# as14120_x31_usb.net
KiCad netlist of a schematic drawn in Altium Designer
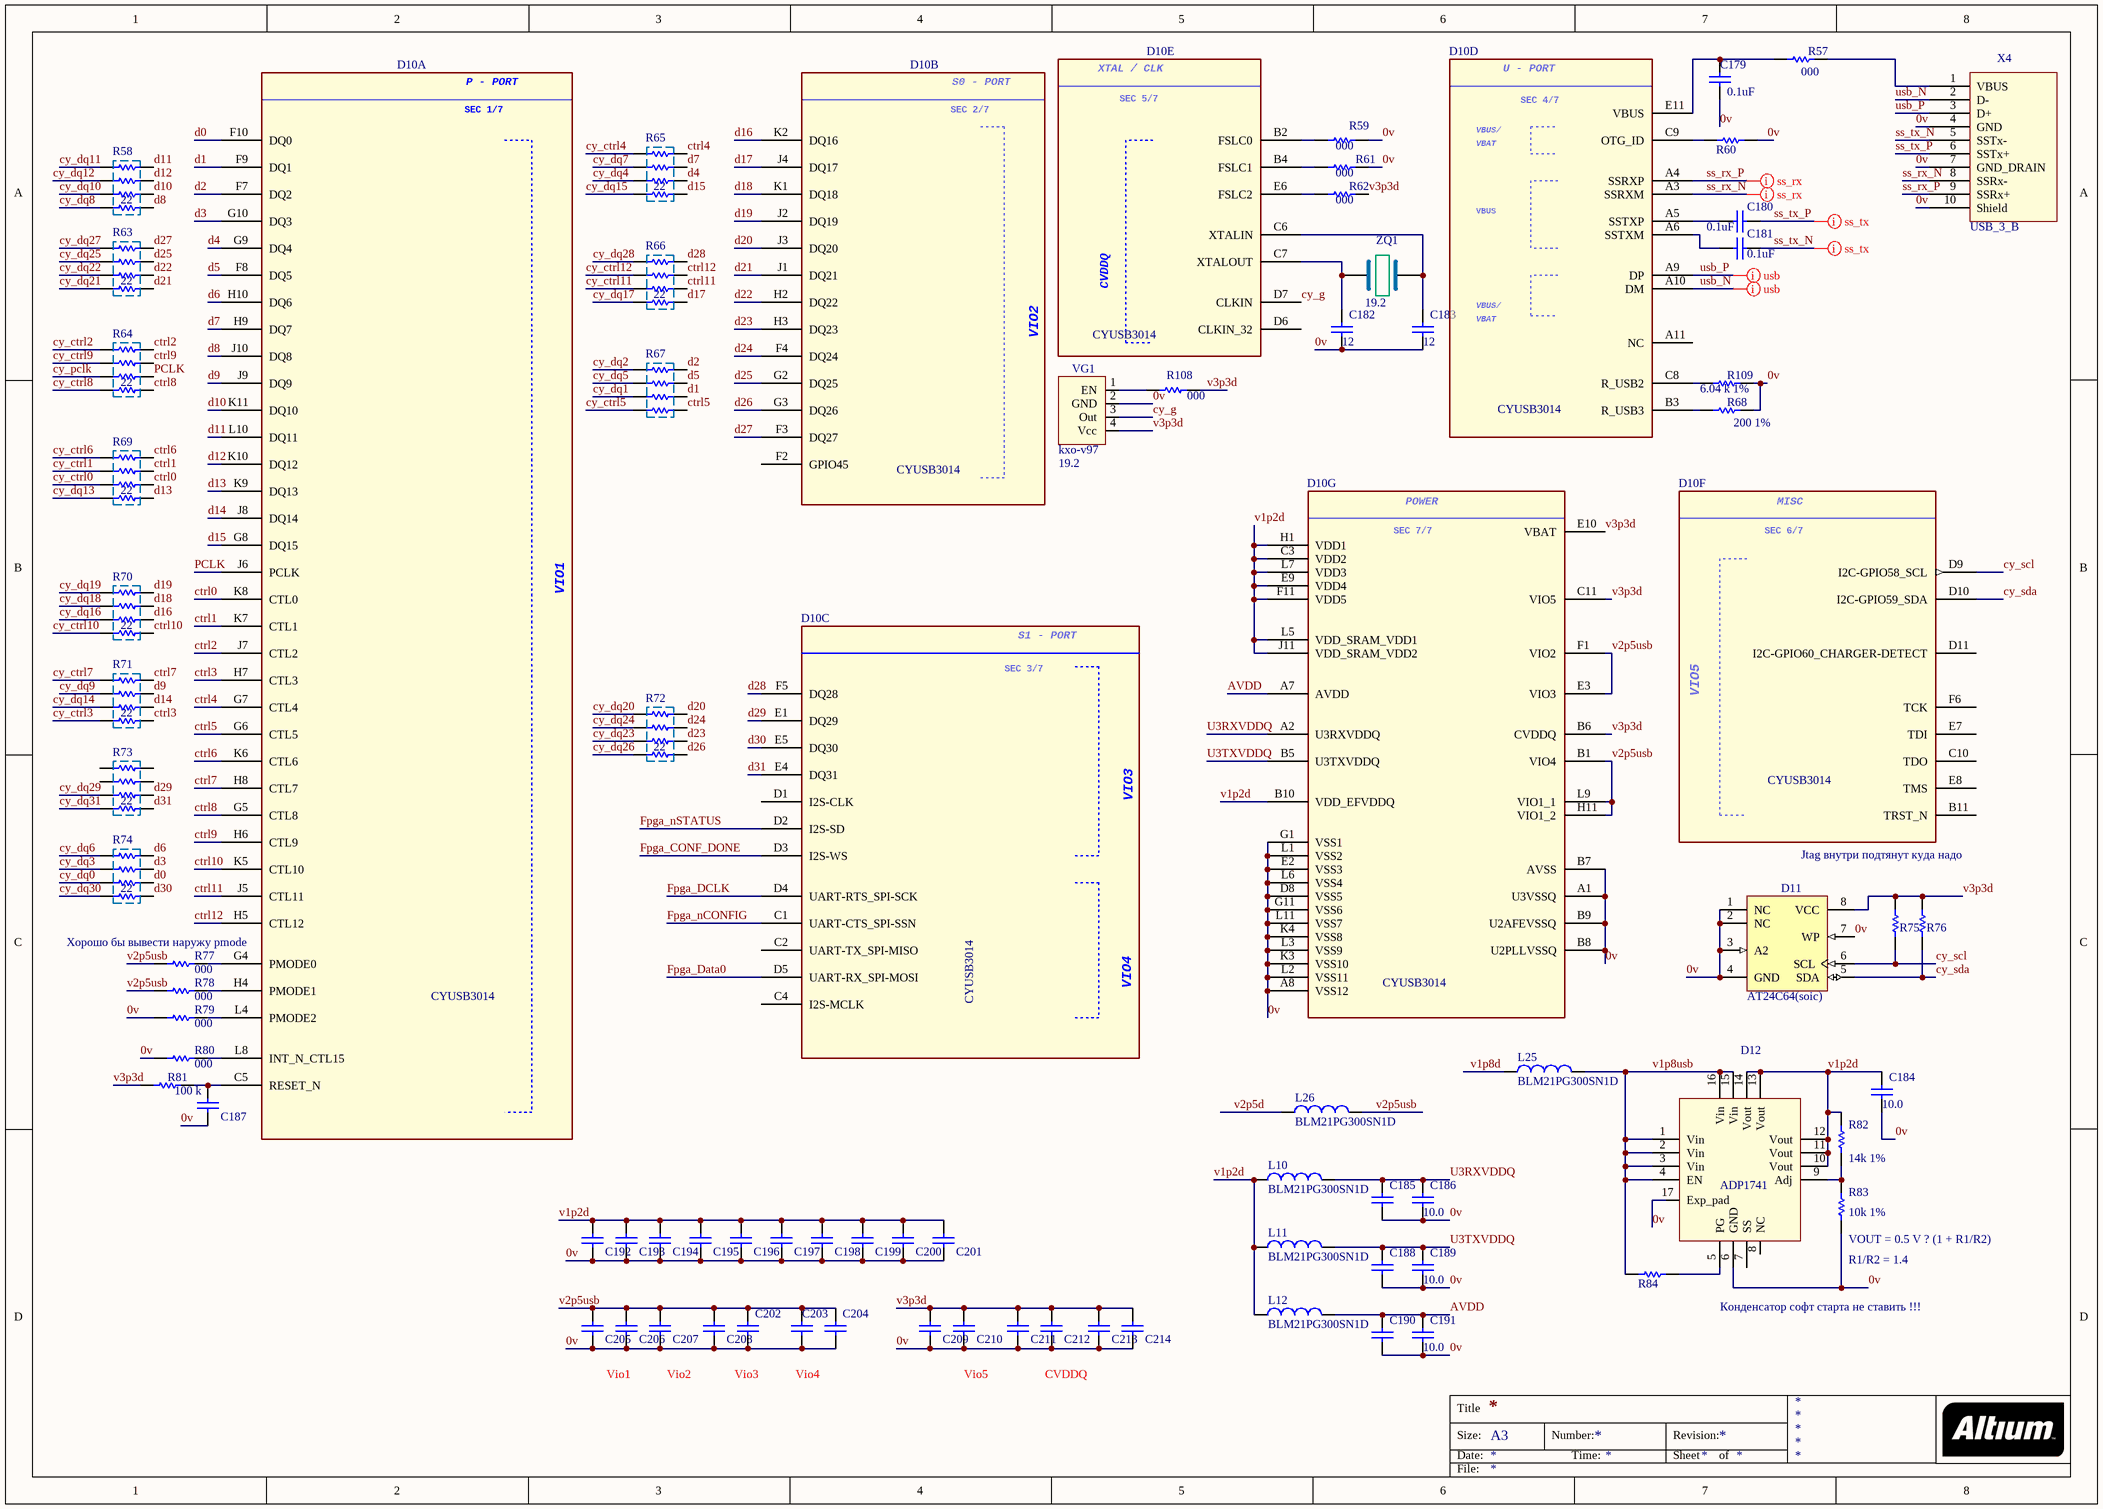
[diagram p0: as14120_x31_usb.SchDoc]

(export (version "E")
  (design (tool "Eeschema 10.0.6"))
  (components
    (comp (ref "C179")
      (value "0.1uF")
      (footprint "CAPC0402(1005)60_M")
      (description "CAP 1uF 10V ±20% 0402 (1005 Metric) Thickness 0.6mm SMD")
      (fields (field (name "TOLERANCE") "±20%") (field (name "Comment") "CAP 1uF 10V 0402(1005)"))
      (libsource (lib "as14120") (part "CAP_0402"))
    )
    (comp (ref "C180")
      (value "0.1uF")
      (footprint "CAPC0402(1005)60_M")
      (description "CAP 1uF 10V ±20% 0402 (1005 Metric) Thickness 0.6mm SMD")
      (fields (field (name "TOLERANCE") "±20%") (field (name "Comment") "CAP 1uF 10V 0402(1005)"))
      (libsource (lib "as14120") (part "CAP_0402"))
    )
    (comp (ref "C181")
      (value "0.1uF")
      (footprint "CAPC0402(1005)60_M")
      (description "CAP 1uF 10V ±20% 0402 (1005 Metric) Thickness 0.6mm SMD")
      (fields (field (name "TOLERANCE") "±20%") (field (name "Comment") "CAP 1uF 10V 0402(1005)"))
      (libsource (lib "as14120") (part "CAP_0402"))
    )
    (comp (ref "C182")
      (value "12")
      (footprint "CAPC0805(2012)100_N")
      (fields (field (name "Comment") "CAP_0805"))
      (libsource (lib "as14120") (part "CAP_0805"))
    )
    (comp (ref "C183")
      (value "12")
      (footprint "CAPC0805(2012)100_N")
      (fields (field (name "Comment") "CAP_0805"))
      (libsource (lib "as14120") (part "CAP_0805"))
    )
    (comp (ref "C184")
      (value "10.0")
      (footprint "CAPC0805(2012)100_N")
      (fields (field (name "Comment") "CAP_0805"))
      (libsource (lib "as14120") (part "CAP_0805"))
    )
    (comp (ref "C185")
      (value "CAP 1uF 10V 0402(1005)")
      (footprint "CAPC0402(1005)60_M")
      (description "CAP 1uF 10V ±20% 0402 (1005 Metric) Thickness 0.6mm SMD")
      (fields (field (name "TOLERANCE") "±20%"))
      (libsource (lib "as14120") (part "CAP_0402"))
    )
    (comp (ref "C186")
      (value "10.0")
      (footprint "CAPC0805(2012)100_N")
      (fields (field (name "Comment") "CAP_0805"))
      (libsource (lib "as14120") (part "CAP_0805"))
    )
    (comp (ref "C187")
      (value "CAP 1uF 10V 0402(1005)")
      (footprint "CAPC0402(1005)60_M")
      (description "CAP 1uF 10V ±20% 0402 (1005 Metric) Thickness 0.6mm SMD")
      (fields (field (name "TOLERANCE") "±20%"))
      (libsource (lib "as14120") (part "CAP_0402"))
    )
    (comp (ref "C188")
      (value "CAP 1uF 10V 0402(1005)")
      (footprint "CAPC0402(1005)60_M")
      (description "CAP 1uF 10V ±20% 0402 (1005 Metric) Thickness 0.6mm SMD")
      (fields (field (name "TOLERANCE") "±20%"))
      (libsource (lib "as14120") (part "CAP_0402"))
    )
    (comp (ref "C189")
      (value "10.0")
      (footprint "CAPC0805(2012)100_N")
      (fields (field (name "Comment") "CAP_0805"))
      (libsource (lib "as14120") (part "CAP_0805"))
    )
    (comp (ref "C190")
      (value "CAP 1uF 10V 0402(1005)")
      (footprint "CAPC0402(1005)60_M")
      (description "CAP 1uF 10V ±20% 0402 (1005 Metric) Thickness 0.6mm SMD")
      (fields (field (name "TOLERANCE") "±20%"))
      (libsource (lib "as14120") (part "CAP_0402"))
    )
    (comp (ref "C191")
      (value "10.0")
      (footprint "CAPC0805(2012)100_N")
      (fields (field (name "Comment") "CAP_0805"))
      (libsource (lib "as14120") (part "CAP_0805"))
    )
    (comp (ref "C192")
      (value "CAP 1uF 10V 0402(1005)")
      (footprint "CAPC0402(1005)60_M")
      (description "CAP 1uF 10V ±20% 0402 (1005 Metric) Thickness 0.6mm SMD")
      (fields (field (name "TOLERANCE") "±20%"))
      (libsource (lib "as14120") (part "CAP_0402"))
    )
    (comp (ref "C193")
      (value "CAP 1uF 10V 0402(1005)")
      (footprint "CAPC0402(1005)60_M")
      (description "CAP 1uF 10V ±20% 0402 (1005 Metric) Thickness 0.6mm SMD")
      (fields (field (name "TOLERANCE") "±20%"))
      (libsource (lib "as14120") (part "CAP_0402"))
    )
    (comp (ref "C194")
      (value "CAP 1uF 10V 0402(1005)")
      (footprint "CAPC0402(1005)60_M")
      (description "CAP 1uF 10V ±20% 0402 (1005 Metric) Thickness 0.6mm SMD")
      (fields (field (name "TOLERANCE") "±20%"))
      (libsource (lib "as14120") (part "CAP_0402"))
    )
    (comp (ref "C195")
      (value "CAP 1uF 10V 0402(1005)")
      (footprint "CAPC0402(1005)60_M")
      (description "CAP 1uF 10V ±20% 0402 (1005 Metric) Thickness 0.6mm SMD")
      (fields (field (name "TOLERANCE") "±20%"))
      (libsource (lib "as14120") (part "CAP_0402"))
    )
    (comp (ref "C196")
      (value "CAP 1uF 10V 0402(1005)")
      (footprint "CAPC0402(1005)60_M")
      (description "CAP 1uF 10V ±20% 0402 (1005 Metric) Thickness 0.6mm SMD")
      (fields (field (name "TOLERANCE") "±20%"))
      (libsource (lib "as14120") (part "CAP_0402"))
    )
    (comp (ref "C197")
      (value "CAP 1uF 10V 0402(1005)")
      (footprint "CAPC0402(1005)60_M")
      (description "CAP 1uF 10V ±20% 0402 (1005 Metric) Thickness 0.6mm SMD")
      (fields (field (name "TOLERANCE") "±20%"))
      (libsource (lib "as14120") (part "CAP_0402"))
    )
    (comp (ref "C198")
      (value "CAP 1uF 10V 0402(1005)")
      (footprint "CAPC0402(1005)60_M")
      (description "CAP 1uF 10V ±20% 0402 (1005 Metric) Thickness 0.6mm SMD")
      (fields (field (name "TOLERANCE") "±20%"))
      (libsource (lib "as14120") (part "CAP_0402"))
    )
    (comp (ref "C199")
      (value "CAP 1uF 10V 0402(1005)")
      (footprint "CAPC0402(1005)60_M")
      (description "CAP 1uF 10V ±20% 0402 (1005 Metric) Thickness 0.6mm SMD")
      (fields (field (name "TOLERANCE") "±20%"))
      (libsource (lib "as14120") (part "CAP_0402"))
    )
    (comp (ref "C200")
      (value "CAP 1uF 10V 0402(1005)")
      (footprint "CAPC0402(1005)60_M")
      (description "CAP 1uF 10V ±20% 0402 (1005 Metric) Thickness 0.6mm SMD")
      (fields (field (name "TOLERANCE") "±20%"))
      (libsource (lib "as14120") (part "CAP_0402"))
    )
    (comp (ref "C201")
      (value "CAP 1uF 10V 0402(1005)")
      (footprint "CAPC0402(1005)60_M")
      (description "CAP 1uF 10V ±20% 0402 (1005 Metric) Thickness 0.6mm SMD")
      (fields (field (name "TOLERANCE") "±20%"))
      (libsource (lib "as14120") (part "CAP_0402"))
    )
    (comp (ref "C202")
      (value "CAP 1uF 10V 0402(1005)")
      (footprint "CAPC0402(1005)60_M")
      (description "CAP 1uF 10V ±20% 0402 (1005 Metric) Thickness 0.6mm SMD")
      (fields (field (name "TOLERANCE") "±20%"))
      (libsource (lib "as14120") (part "CAP_0402"))
    )
    (comp (ref "C203")
      (value "CAP 1uF 10V 0402(1005)")
      (footprint "CAPC0402(1005)60_M")
      (description "CAP 1uF 10V ±20% 0402 (1005 Metric) Thickness 0.6mm SMD")
      (fields (field (name "TOLERANCE") "±20%"))
      (libsource (lib "as14120") (part "CAP_0402"))
    )
    (comp (ref "C204")
      (value "CAP 1uF 10V 0402(1005)")
      (footprint "CAPC0402(1005)60_M")
      (description "CAP 1uF 10V ±20% 0402 (1005 Metric) Thickness 0.6mm SMD")
      (fields (field (name "TOLERANCE") "±20%"))
      (libsource (lib "as14120") (part "CAP_0402"))
    )
    (comp (ref "C205")
      (value "CAP 1uF 10V 0402(1005)")
      (footprint "CAPC0402(1005)60_M")
      (description "CAP 1uF 10V ±20% 0402 (1005 Metric) Thickness 0.6mm SMD")
      (fields (field (name "TOLERANCE") "±20%"))
      (libsource (lib "as14120") (part "CAP_0402"))
    )
    (comp (ref "C206")
      (value "CAP 1uF 10V 0402(1005)")
      (footprint "CAPC0402(1005)60_M")
      (description "CAP 1uF 10V ±20% 0402 (1005 Metric) Thickness 0.6mm SMD")
      (fields (field (name "TOLERANCE") "±20%"))
      (libsource (lib "as14120") (part "CAP_0402"))
    )
    (comp (ref "C207")
      (value "CAP 1uF 10V 0402(1005)")
      (footprint "CAPC0402(1005)60_M")
      (description "CAP 1uF 10V ±20% 0402 (1005 Metric) Thickness 0.6mm SMD")
      (fields (field (name "TOLERANCE") "±20%"))
      (libsource (lib "as14120") (part "CAP_0402"))
    )
    (comp (ref "C208")
      (value "CAP 1uF 10V 0402(1005)")
      (footprint "CAPC0402(1005)60_M")
      (description "CAP 1uF 10V ±20% 0402 (1005 Metric) Thickness 0.6mm SMD")
      (fields (field (name "TOLERANCE") "±20%"))
      (libsource (lib "as14120") (part "CAP_0402"))
    )
    (comp (ref "C209")
      (value "CAP 1uF 10V 0402(1005)")
      (footprint "CAPC0402(1005)60_M")
      (description "CAP 1uF 10V ±20% 0402 (1005 Metric) Thickness 0.6mm SMD")
      (fields (field (name "TOLERANCE") "±20%"))
      (libsource (lib "as14120") (part "CAP_0402"))
    )
    (comp (ref "C210")
      (value "CAP 1uF 10V 0402(1005)")
      (footprint "CAPC0402(1005)60_M")
      (description "CAP 1uF 10V ±20% 0402 (1005 Metric) Thickness 0.6mm SMD")
      (fields (field (name "TOLERANCE") "±20%"))
      (libsource (lib "as14120") (part "CAP_0402"))
    )
    (comp (ref "C211")
      (value "CAP 1uF 10V 0402(1005)")
      (footprint "CAPC0402(1005)60_M")
      (description "CAP 1uF 10V ±20% 0402 (1005 Metric) Thickness 0.6mm SMD")
      (fields (field (name "TOLERANCE") "±20%"))
      (libsource (lib "as14120") (part "CAP_0402"))
    )
    (comp (ref "C212")
      (value "CAP 1uF 10V 0402(1005)")
      (footprint "CAPC0402(1005)60_M")
      (description "CAP 1uF 10V ±20% 0402 (1005 Metric) Thickness 0.6mm SMD")
      (fields (field (name "TOLERANCE") "±20%"))
      (libsource (lib "as14120") (part "CAP_0402"))
    )
    (comp (ref "C213")
      (value "CAP 1uF 10V 0402(1005)")
      (footprint "CAPC0402(1005)60_M")
      (description "CAP 1uF 10V ±20% 0402 (1005 Metric) Thickness 0.6mm SMD")
      (fields (field (name "TOLERANCE") "±20%"))
      (libsource (lib "as14120") (part "CAP_0402"))
    )
    (comp (ref "C214")
      (value "CAP 1uF 10V 0402(1005)")
      (footprint "CAPC0402(1005)60_M")
      (description "CAP 1uF 10V ±20% 0402 (1005 Metric) Thickness 0.6mm SMD")
      (fields (field (name "TOLERANCE") "±20%"))
      (libsource (lib "as14120") (part "CAP_0402"))
    )
    (comp (ref "D10")
      (value "CYUSB3014")
      (footprint "BGA121C80P11X11")
      (libsource (lib "as14120") (part "CYUSB3014-BZXC"))
    )
    (comp (ref "D11")
      (value "AT24C64(soic)")
      (footprint "8S1_N")
      (libsource (lib "Atmel Serial EEPROM") (part "AT24C08BN-SP25-T"))
    )
    (comp (ref "D12") (value "ADP1741") (footprint "CP-16-4_N") (libsource (lib "as14120") (part "ADP1741")))
    (comp (ref "L10")
      (value "BLM21PG300SN1D")
      (footprint "CAPC0805(2012)100_N")
      (libsource (lib "as14120") (part "Ferrite_beat"))
    )
    (comp (ref "L11")
      (value "BLM21PG300SN1D")
      (footprint "CAPC0805(2012)100_N")
      (libsource (lib "as14120") (part "Ferrite_beat"))
    )
    (comp (ref "L12")
      (value "BLM21PG300SN1D")
      (footprint "CAPC0805(2012)100_N")
      (libsource (lib "as14120") (part "Ferrite_beat"))
    )
    (comp (ref "L25")
      (value "BLM21PG300SN1D")
      (footprint "CAPC0805(2012)100_N")
      (libsource (lib "as14120") (part "Ferrite_beat"))
    )
    (comp (ref "L26")
      (value "BLM21PG300SN1D")
      (footprint "CAPC0805(2012)100_N")
      (libsource (lib "as14120") (part "Ferrite_beat"))
    )
    (comp (ref "R57")
      (value "000")
      (footprint "RESC0805(2012)_L")
      (description "1K 0.125W 1% 0805 (2012 Metric)  SMD")
      (fields (field (name "TOLERANCE") "1 %") (field (name "POWER") "0.125 W"))
      (libsource (lib "as14120") (part "RES_0805"))
    )
    (comp (ref "R58") (value "22") (footprint "CAY16") (libsource (lib "as14120") (part "cay16-J4")))
    (comp (ref "R59")
      (value "000")
      (footprint "RESC0603(1608)_L")
      (description "1K 0.1W 5% 0603 (1608 Metric)  SMD")
      (fields (field (name "TOLERANCE") "5 %") (field (name "POWER") "0.1 W"))
      (libsource (lib "as14120") (part "RES_0603"))
    )
    (comp (ref "R60")
      (value "???")
      (footprint "RESC0603(1608)_L")
      (description "1K 0.1W 5% 0603 (1608 Metric)  SMD")
      (fields (field (name "TOLERANCE") "5 %") (field (name "POWER") "0.1 W"))
      (libsource (lib "as14120") (part "RES_0603"))
    )
    (comp (ref "R61")
      (value "000")
      (footprint "RESC0603(1608)_L")
      (description "1K 0.1W 5% 0603 (1608 Metric)  SMD")
      (fields (field (name "TOLERANCE") "5 %") (field (name "POWER") "0.1 W"))
      (libsource (lib "as14120") (part "RES_0603"))
    )
    (comp (ref "R62")
      (value "000")
      (footprint "RESC0603(1608)_L")
      (description "1K 0.1W 5% 0603 (1608 Metric)  SMD")
      (fields (field (name "TOLERANCE") "5 %") (field (name "POWER") "0.1 W"))
      (libsource (lib "as14120") (part "RES_0603"))
    )
    (comp (ref "R63") (value "22") (footprint "CAY16") (libsource (lib "as14120") (part "cay16-J4")))
    (comp (ref "R64") (value "22") (footprint "CAY16") (libsource (lib "as14120") (part "cay16-J4")))
    (comp (ref "R65") (value "22") (footprint "CAY16") (libsource (lib "as14120") (part "cay16-J4")))
    (comp (ref "R66") (value "22") (footprint "CAY16") (libsource (lib "as14120") (part "cay16-J4")))
    (comp (ref "R67") (value "~") (footprint "CAY16") (libsource (lib "as14120") (part "cay16-J4")))
    (comp (ref "R68")
      (value "200 1%")
      (footprint "RESC0805(2012)_L")
      (description "1K 0.125W 1% 0805 (2012 Metric)  SMD")
      (fields (field (name "TOLERANCE") "1 %") (field (name "POWER") "0.125 W"))
      (libsource (lib "as14120") (part "RES_0805"))
    )
    (comp (ref "R69") (value "22") (footprint "CAY16") (libsource (lib "as14120") (part "cay16-J4")))
    (comp (ref "R70") (value "22") (footprint "CAY16") (libsource (lib "as14120") (part "cay16-J4")))
    (comp (ref "R71") (value "22") (footprint "CAY16") (libsource (lib "as14120") (part "cay16-J4")))
    (comp (ref "R72") (value "22") (footprint "CAY16") (libsource (lib "as14120") (part "cay16-J4")))
    (comp (ref "R73") (value "22") (footprint "CAY16") (libsource (lib "as14120") (part "cay16-J4")))
    (comp (ref "R74") (value "22") (footprint "CAY16") (libsource (lib "as14120") (part "cay16-J4")))
    (comp (ref "R75")
      (value "1K 5% 0603(1608)")
      (footprint "RESC0603(1608)_L")
      (description "1K 0.1W 5% 0603 (1608 Metric)  SMD")
      (fields (field (name "TOLERANCE") "5 %") (field (name "POWER") "0.1 W"))
      (libsource (lib "as14120") (part "RES_0603"))
    )
    (comp (ref "R76")
      (value "1K 5% 0603(1608)")
      (footprint "RESC0603(1608)_L")
      (description "1K 0.1W 5% 0603 (1608 Metric)  SMD")
      (fields (field (name "TOLERANCE") "5 %") (field (name "POWER") "0.1 W"))
      (libsource (lib "as14120") (part "RES_0603"))
    )
    (comp (ref "R77")
      (value "000")
      (footprint "RESC0603(1608)_L")
      (description "1K 0.1W 5% 0603 (1608 Metric)  SMD")
      (fields (field (name "TOLERANCE") "5 %") (field (name "POWER") "0.1 W"))
      (libsource (lib "as14120") (part "RES_0603"))
    )
    (comp (ref "R78")
      (value "000")
      (footprint "RESC0603(1608)_L")
      (description "1K 0.1W 5% 0603 (1608 Metric)  SMD")
      (fields (field (name "TOLERANCE") "5 %") (field (name "POWER") "0.1 W"))
      (libsource (lib "as14120") (part "RES_0603"))
    )
    (comp (ref "R79")
      (value "000")
      (footprint "RESC0603(1608)_L")
      (description "1K 0.1W 5% 0603 (1608 Metric)  SMD")
      (fields (field (name "TOLERANCE") "5 %") (field (name "POWER") "0.1 W"))
      (libsource (lib "as14120") (part "RES_0603"))
    )
    (comp (ref "R80")
      (value "000")
      (footprint "RESC0603(1608)_L")
      (description "1K 0.1W 5% 0603 (1608 Metric)  SMD")
      (fields (field (name "TOLERANCE") "5 %") (field (name "POWER") "0.1 W"))
      (libsource (lib "as14120") (part "RES_0603"))
    )
    (comp (ref "R81")
      (value "100 k")
      (footprint "RESC0603(1608)_L")
      (description "1K 0.1W 5% 0603 (1608 Metric)  SMD")
      (fields (field (name "TOLERANCE") "5 %") (field (name "POWER") "0.1 W"))
      (libsource (lib "as14120") (part "RES_0603"))
    )
    (comp (ref "R82")
      (value "14k 1%")
      (footprint "RESC0805(2012)_L")
      (description "1K 0.125W 1% 0805 (2012 Metric)  SMD")
      (fields (field (name "TOLERANCE") "1 %") (field (name "POWER") "0.125 W"))
      (libsource (lib "as14120") (part "RES_0805"))
    )
    (comp (ref "R83")
      (value "10k 1%")
      (footprint "RESC0805(2012)_L")
      (description "1K 0.125W 1% 0805 (2012 Metric)  SMD")
      (fields (field (name "TOLERANCE") "1 %") (field (name "POWER") "0.125 W"))
      (libsource (lib "as14120") (part "RES_0805"))
    )
    (comp (ref "R84")
      (value "1K 5% 0603(1608)")
      (footprint "RESC0603(1608)_L")
      (description "1K 0.1W 5% 0603 (1608 Metric)  SMD")
      (fields (field (name "TOLERANCE") "5 %") (field (name "POWER") "0.1 W"))
      (libsource (lib "as14120") (part "RES_0603"))
    )
    (comp (ref "R108")
      (value "000")
      (footprint "RESC0603(1608)_L")
      (description "1K 0.1W 5% 0603 (1608 Metric)  SMD")
      (fields (field (name "TOLERANCE") "5 %") (field (name "POWER") "0.1 W"))
      (libsource (lib "as14120") (part "RES_0603"))
    )
    (comp (ref "R109")
      (value "6.04 k 1%")
      (footprint "RESC0805(2012)_L")
      (description "1K 0.125W 1% 0805 (2012 Metric)  SMD")
      (fields (field (name "TOLERANCE") "1 %") (field (name "POWER") "0.125 W"))
      (libsource (lib "as14120") (part "RES_0805"))
    )
    (comp (ref "VG1")
      (value "kxo-v97")
      (footprint "kxo-v97")
      (fields (field (name "ALTIUM_VALUE") "19.2"))
      (libsource (lib "as14120") (part "kxo-v97"))
    )
    (comp (ref "X4") (value "USB_3_B") (footprint "USB3_B") (libsource (lib "as14120") (part "USB_3_B")))
    (comp (ref "ZQ1")
      (value "19.2")
      (footprint "BCY-W2/E4.7")
      (fields (field (name "Comment") "Resonator"))
      (libsource (lib "as14120") (part "Resonator"))
    )
  )
  (nets
    (net (code "1") (name "/0v") (class "Default")
      (node (ref "C179") (pin "2") (pinfunction "2_2") (pintype "passive"))
      (node (ref "C182") (pin "1") (pinfunction "1_1") (pintype "passive"))
      (node (ref "C183") (pin "1") (pinfunction "1_1") (pintype "passive"))
      (node (ref "C184") (pin "1") (pinfunction "1_1") (pintype "passive"))
      (node (ref "C185") (pin "1") (pinfunction "1_1") (pintype "passive"))
      (node (ref "C186") (pin "1") (pinfunction "1_1") (pintype "passive"))
      (node (ref "C187") (pin "1") (pinfunction "1_1") (pintype "passive"))
      (node (ref "C188") (pin "1") (pinfunction "1_1") (pintype "passive"))
      (node (ref "C189") (pin "1") (pinfunction "1_1") (pintype "passive"))
      (node (ref "C190") (pin "1") (pinfunction "1_1") (pintype "passive"))
      (node (ref "C191") (pin "1") (pinfunction "1_1") (pintype "passive"))
      (node (ref "C192") (pin "1") (pinfunction "1_1") (pintype "passive"))
      (node (ref "C193") (pin "1") (pinfunction "1_1") (pintype "passive"))
      (node (ref "C194") (pin "1") (pinfunction "1_1") (pintype "passive"))
      (node (ref "C195") (pin "1") (pinfunction "1_1") (pintype "passive"))
      (node (ref "C196") (pin "1") (pinfunction "1_1") (pintype "passive"))
      (node (ref "C197") (pin "1") (pinfunction "1_1") (pintype "passive"))
      (node (ref "C198") (pin "1") (pinfunction "1_1") (pintype "passive"))
      (node (ref "C199") (pin "1") (pinfunction "1_1") (pintype "passive"))
      (node (ref "C200") (pin "1") (pinfunction "1_1") (pintype "passive"))
      (node (ref "C201") (pin "1") (pinfunction "1_1") (pintype "passive"))
      (node (ref "C202") (pin "1") (pinfunction "1_1") (pintype "passive"))
      (node (ref "C203") (pin "1") (pinfunction "1_1") (pintype "passive"))
      (node (ref "C204") (pin "1") (pinfunction "1_1") (pintype "passive"))
      (node (ref "C205") (pin "1") (pinfunction "1_1") (pintype "passive"))
      (node (ref "C206") (pin "1") (pinfunction "1_1") (pintype "passive"))
      (node (ref "C207") (pin "1") (pinfunction "1_1") (pintype "passive"))
      (node (ref "C208") (pin "1") (pinfunction "1_1") (pintype "passive"))
      (node (ref "C209") (pin "1") (pinfunction "1_1") (pintype "passive"))
      (node (ref "C210") (pin "1") (pinfunction "1_1") (pintype "passive"))
      (node (ref "C211") (pin "1") (pinfunction "1_1") (pintype "passive"))
      (node (ref "C212") (pin "1") (pinfunction "1_1") (pintype "passive"))
      (node (ref "C213") (pin "1") (pinfunction "1_1") (pintype "passive"))
      (node (ref "C214") (pin "1") (pinfunction "1_1") (pintype "passive"))
      (node (ref "D10") (pin "A1") (pinfunction "U3VSSQ_A1") (pintype "passive"))
      (node (ref "D10") (pin "A8") (pinfunction "VSS12_A8") (pintype "passive"))
      (node (ref "D10") (pin "B7") (pinfunction "AVSS_B7") (pintype "passive"))
      (node (ref "D10") (pin "B8") (pinfunction "U2PLLVSSQ_B8") (pintype "passive"))
      (node (ref "D10") (pin "B9") (pinfunction "U2AFEVSSQ_B9") (pintype "passive"))
      (node (ref "D10") (pin "D8") (pinfunction "VSS5_D8") (pintype "passive"))
      (node (ref "D10") (pin "E2") (pinfunction "VSS3_E2") (pintype "passive"))
      (node (ref "D10") (pin "G1") (pinfunction "VSS1_G1") (pintype "passive"))
      (node (ref "D10") (pin "G11") (pinfunction "VSS6_G11") (pintype "passive"))
      (node (ref "D10") (pin "K3") (pinfunction "VSS10_K3") (pintype "passive"))
      (node (ref "D10") (pin "K4") (pinfunction "VSS8_K4") (pintype "passive"))
      (node (ref "D10") (pin "L1") (pinfunction "VSS2_L1") (pintype "passive"))
      (node (ref "D10") (pin "L11") (pinfunction "VSS7_L11") (pintype "passive"))
      (node (ref "D10") (pin "L2") (pinfunction "VSS11_L2") (pintype "passive"))
      (node (ref "D10") (pin "L3") (pinfunction "VSS9_L3") (pintype "passive"))
      (node (ref "D10") (pin "L6") (pinfunction "VSS4_L6") (pintype "passive"))
      (node (ref "D11") (pin "1") (pinfunction "NC_1") (pintype "passive"))
      (node (ref "D11") (pin "2") (pinfunction "NC_2") (pintype "passive"))
      (node (ref "D11") (pin "3") (pinfunction "A2_3") (pintype "input"))
      (node (ref "D11") (pin "4") (pinfunction "GND_4") (pintype "power_in"))
      (node (ref "D11") (pin "7") (pinfunction "WP_7") (pintype "input"))
      (node (ref "D12") (pin "17") (pinfunction "Exp_pad_17") (pintype "passive"))
      (node (ref "D12") (pin "6") (pinfunction "GND_6") (pintype "passive"))
      (node (ref "R109") (pin "2") (pinfunction "2_2") (pintype "passive"))
      (node (ref "R59") (pin "1") (pinfunction "1_1") (pintype "passive"))
      (node (ref "R60") (pin "2") (pinfunction "2_2") (pintype "passive"))
      (node (ref "R61") (pin "1") (pinfunction "1_1") (pintype "passive"))
      (node (ref "R68") (pin "2") (pinfunction "2_2") (pintype "passive"))
      (node (ref "R79") (pin "2") (pinfunction "2_2") (pintype "passive"))
      (node (ref "R80") (pin "2") (pinfunction "2_2") (pintype "passive"))
      (node (ref "R83") (pin "1") (pinfunction "1_1") (pintype "passive"))
      (node (ref "VG1") (pin "2") (pinfunction "GND_2") (pintype "passive"))
      (node (ref "X4") (pin "10") (pinfunction "Shield_10") (pintype "passive"))
      (node (ref "X4") (pin "4") (pinfunction "GND_4") (pintype "passive"))
      (node (ref "X4") (pin "7") (pinfunction "GND_DRAIN_7") (pintype "passive"))
    )
    (net (code "2") (name "/AVDD") (class "Default")
      (node (ref "C190") (pin "2") (pinfunction "2_2") (pintype "passive"))
      (node (ref "C191") (pin "2") (pinfunction "2_2") (pintype "passive"))
      (node (ref "D10") (pin "A7") (pinfunction "AVDD_A7") (pintype "passive"))
      (node (ref "L12") (pin "2") (pinfunction "2_2") (pintype "passive"))
    )
    (net (code "3") (name "/Fpga_CONF_DONE") (class "Default")
      (node (ref "D10") (pin "D3") (pinfunction "I2S-WS_D3") (pintype "passive"))
    )
    (net (code "4") (name "/Fpga_DCLK") (class "Default")
      (node (ref "D10") (pin "D4") (pinfunction "UART-RTS_SPI-SCK_D4") (pintype "passive"))
    )
    (net (code "5") (name "/Fpga_Data0") (class "Default")
      (node (ref "D10") (pin "D5") (pinfunction "UART-RX_SPI-MOSI_D5") (pintype "passive"))
    )
    (net (code "6") (name "/Fpga_nCONFIG") (class "Default")
      (node (ref "D10") (pin "C1") (pinfunction "UART-CTS_SPI-SSN_C1") (pintype "passive"))
    )
    (net (code "7") (name "/Fpga_nSTATUS") (class "Default")
      (node (ref "D10") (pin "D2") (pinfunction "I2S-SD_D2") (pintype "passive"))
    )
    (net (code "8") (name "/PCLK") (class "Default")
      (node (ref "D10") (pin "J6") (pinfunction "PCLK_J6") (pintype "passive"))
      (node (ref "R64") (pin "6") (pinfunction "6_6") (pintype "passive"))
    )
    (net (code "9") (name "/U3RXVDDQ") (class "Default")
      (node (ref "C185") (pin "2") (pinfunction "2_2") (pintype "passive"))
      (node (ref "C186") (pin "2") (pinfunction "2_2") (pintype "passive"))
      (node (ref "D10") (pin "A2") (pinfunction "U3RXVDDQ_A2") (pintype "passive"))
      (node (ref "L10") (pin "2") (pinfunction "2_2") (pintype "passive"))
    )
    (net (code "10") (name "/U3TXVDDQ") (class "Default")
      (node (ref "C188") (pin "2") (pinfunction "2_2") (pintype "passive"))
      (node (ref "C189") (pin "2") (pinfunction "2_2") (pintype "passive"))
      (node (ref "D10") (pin "B5") (pinfunction "U3TXVDDQ_B5") (pintype "passive"))
      (node (ref "L11") (pin "2") (pinfunction "2_2") (pintype "passive"))
    )
    (net (code "11") (name "/ctrl0") (class "Default")
      (node (ref "D10") (pin "K8") (pinfunction "CTL0_K8") (pintype "passive"))
      (node (ref "R69") (pin "6") (pinfunction "6_6") (pintype "passive"))
    )
    (net (code "12") (name "/ctrl1") (class "Default")
      (node (ref "D10") (pin "K7") (pinfunction "CTL1_K7") (pintype "passive"))
      (node (ref "R69") (pin "7") (pinfunction "7_7") (pintype "passive"))
    )
    (net (code "13") (name "/ctrl2") (class "Default")
      (node (ref "D10") (pin "J7") (pinfunction "CTL2_J7") (pintype "passive"))
      (node (ref "R64") (pin "8") (pinfunction "8_8") (pintype "passive"))
    )
    (net (code "14") (name "/ctrl3") (class "Default")
      (node (ref "D10") (pin "H7") (pinfunction "CTL3_H7") (pintype "passive"))
      (node (ref "R71") (pin "5") (pinfunction "5_5") (pintype "passive"))
    )
    (net (code "15") (name "/ctrl4") (class "Default")
      (node (ref "D10") (pin "G7") (pinfunction "CTL4_G7") (pintype "passive"))
      (node (ref "R65") (pin "8") (pinfunction "8_8") (pintype "passive"))
    )
    (net (code "16") (name "/ctrl5") (class "Default")
      (node (ref "D10") (pin "G6") (pinfunction "CTL5_G6") (pintype "passive"))
      (node (ref "R67") (pin "5") (pinfunction "5_5") (pintype "passive"))
    )
    (net (code "17") (name "/ctrl6") (class "Default")
      (node (ref "D10") (pin "K6") (pinfunction "CTL6_K6") (pintype "passive"))
      (node (ref "R69") (pin "8") (pinfunction "8_8") (pintype "passive"))
    )
    (net (code "18") (name "/ctrl7") (class "Default")
      (node (ref "D10") (pin "H8") (pinfunction "CTL7_H8") (pintype "passive"))
      (node (ref "R71") (pin "8") (pinfunction "8_8") (pintype "passive"))
    )
    (net (code "19") (name "/ctrl8") (class "Default")
      (node (ref "D10") (pin "G5") (pinfunction "CTL8_G5") (pintype "passive"))
      (node (ref "R64") (pin "5") (pinfunction "5_5") (pintype "passive"))
    )
    (net (code "20") (name "/ctrl9") (class "Default")
      (node (ref "D10") (pin "H6") (pinfunction "CTL9_H6") (pintype "passive"))
      (node (ref "R64") (pin "7") (pinfunction "7_7") (pintype "passive"))
    )
    (net (code "21") (name "/ctrl10") (class "Default")
      (node (ref "D10") (pin "K5") (pinfunction "CTL10_K5") (pintype "passive"))
      (node (ref "R70") (pin "5") (pinfunction "5_5") (pintype "passive"))
    )
    (net (code "22") (name "/ctrl11") (class "Default")
      (node (ref "D10") (pin "J5") (pinfunction "CTL11_J5") (pintype "passive"))
      (node (ref "R66") (pin "6") (pinfunction "6_6") (pintype "passive"))
    )
    (net (code "23") (name "/ctrl12") (class "Default")
      (node (ref "D10") (pin "H5") (pinfunction "CTL12_H5") (pintype "passive"))
      (node (ref "R66") (pin "7") (pinfunction "7_7") (pintype "passive"))
    )
    (net (code "24") (name "/cy_ctrl0") (class "Default")
      (node (ref "R69") (pin "3") (pinfunction "3_3") (pintype "passive"))
    )
    (net (code "25") (name "/cy_ctrl1") (class "Default")
      (node (ref "R69") (pin "2") (pinfunction "2_2") (pintype "passive"))
    )
    (net (code "26") (name "/cy_ctrl2") (class "Default")
      (node (ref "R64") (pin "1") (pinfunction "1_1") (pintype "passive"))
    )
    (net (code "27") (name "/cy_ctrl3") (class "Default")
      (node (ref "R71") (pin "4") (pinfunction "4_4") (pintype "passive"))
    )
    (net (code "28") (name "/cy_ctrl4") (class "Default")
      (node (ref "R65") (pin "1") (pinfunction "1_1") (pintype "passive"))
    )
    (net (code "29") (name "/cy_ctrl5") (class "Default")
      (node (ref "R67") (pin "4") (pinfunction "4_4") (pintype "passive"))
    )
    (net (code "30") (name "/cy_ctrl6") (class "Default")
      (node (ref "R69") (pin "1") (pinfunction "1_1") (pintype "passive"))
    )
    (net (code "31") (name "/cy_ctrl7") (class "Default")
      (node (ref "R71") (pin "1") (pinfunction "1_1") (pintype "passive"))
    )
    (net (code "32") (name "/cy_ctrl8") (class "Default")
      (node (ref "R64") (pin "4") (pinfunction "4_4") (pintype "passive"))
    )
    (net (code "33") (name "/cy_ctrl9") (class "Default")
      (node (ref "R64") (pin "2") (pinfunction "2_2") (pintype "passive"))
    )
    (net (code "34") (name "/cy_ctrl10") (class "Default")
      (node (ref "R70") (pin "4") (pinfunction "4_4") (pintype "passive"))
    )
    (net (code "35") (name "/cy_ctrl11") (class "Default")
      (node (ref "R66") (pin "3") (pinfunction "3_3") (pintype "passive"))
    )
    (net (code "36") (name "/cy_ctrl12") (class "Default")
      (node (ref "R66") (pin "2") (pinfunction "2_2") (pintype "passive"))
    )
    (net (code "37") (name "/cy_dq0") (class "Default")
      (node (ref "R74") (pin "3") (pinfunction "3_3") (pintype "passive"))
    )
    (net (code "38") (name "/cy_dq1") (class "Default")
      (node (ref "R67") (pin "3") (pinfunction "3_3") (pintype "passive"))
    )
    (net (code "39") (name "/cy_dq2") (class "Default")
      (node (ref "R67") (pin "1") (pinfunction "1_1") (pintype "passive"))
    )
    (net (code "40") (name "/cy_dq3") (class "Default")
      (node (ref "R74") (pin "2") (pinfunction "2_2") (pintype "passive"))
    )
    (net (code "41") (name "/cy_dq4") (class "Default")
      (node (ref "R65") (pin "3") (pinfunction "3_3") (pintype "passive"))
    )
    (net (code "42") (name "/cy_dq5") (class "Default")
      (node (ref "R67") (pin "2") (pinfunction "2_2") (pintype "passive"))
    )
    (net (code "43") (name "/cy_dq6") (class "Default")
      (node (ref "R74") (pin "1") (pinfunction "1_1") (pintype "passive"))
    )
    (net (code "44") (name "/cy_dq7") (class "Default")
      (node (ref "R65") (pin "2") (pinfunction "2_2") (pintype "passive"))
    )
    (net (code "45") (name "/cy_dq8") (class "Default")
      (node (ref "R58") (pin "4") (pinfunction "4_4") (pintype "passive"))
    )
    (net (code "46") (name "/cy_dq9") (class "Default")
      (node (ref "R71") (pin "2") (pinfunction "2_2") (pintype "passive"))
    )
    (net (code "47") (name "/cy_dq10") (class "Default")
      (node (ref "R58") (pin "3") (pinfunction "3_3") (pintype "passive"))
    )
    (net (code "48") (name "/cy_dq11") (class "Default")
      (node (ref "R58") (pin "1") (pinfunction "1_1") (pintype "passive"))
    )
    (net (code "49") (name "/cy_dq12") (class "Default")
      (node (ref "R58") (pin "2") (pinfunction "2_2") (pintype "passive"))
    )
    (net (code "50") (name "/cy_dq13") (class "Default")
      (node (ref "R69") (pin "4") (pinfunction "4_4") (pintype "passive"))
    )
    (net (code "51") (name "/cy_dq14") (class "Default")
      (node (ref "R71") (pin "3") (pinfunction "3_3") (pintype "passive"))
    )
    (net (code "52") (name "/cy_dq15") (class "Default")
      (node (ref "R65") (pin "4") (pinfunction "4_4") (pintype "passive"))
    )
    (net (code "53") (name "/cy_dq16") (class "Default")
      (node (ref "R70") (pin "3") (pinfunction "3_3") (pintype "passive"))
    )
    (net (code "54") (name "/cy_dq17") (class "Default")
      (node (ref "R66") (pin "4") (pinfunction "4_4") (pintype "passive"))
    )
    (net (code "55") (name "/cy_dq18") (class "Default")
      (node (ref "R70") (pin "2") (pinfunction "2_2") (pintype "passive"))
    )
    (net (code "56") (name "/cy_dq19") (class "Default")
      (node (ref "R70") (pin "1") (pinfunction "1_1") (pintype "passive"))
    )
    (net (code "57") (name "/cy_dq20") (class "Default")
      (node (ref "R72") (pin "1") (pinfunction "1_1") (pintype "passive"))
    )
    (net (code "58") (name "/cy_dq21") (class "Default")
      (node (ref "R63") (pin "4") (pinfunction "4_4") (pintype "passive"))
    )
    (net (code "59") (name "/cy_dq22") (class "Default")
      (node (ref "R63") (pin "3") (pinfunction "3_3") (pintype "passive"))
    )
    (net (code "60") (name "/cy_dq23") (class "Default")
      (node (ref "R72") (pin "3") (pinfunction "3_3") (pintype "passive"))
    )
    (net (code "61") (name "/cy_dq24") (class "Default")
      (node (ref "R72") (pin "2") (pinfunction "2_2") (pintype "passive"))
    )
    (net (code "62") (name "/cy_dq25") (class "Default")
      (node (ref "R63") (pin "2") (pinfunction "2_2") (pintype "passive"))
    )
    (net (code "63") (name "/cy_dq26") (class "Default")
      (node (ref "R72") (pin "4") (pinfunction "4_4") (pintype "passive"))
    )
    (net (code "64") (name "/cy_dq27") (class "Default")
      (node (ref "R63") (pin "1") (pinfunction "1_1") (pintype "passive"))
    )
    (net (code "65") (name "/cy_dq28") (class "Default")
      (node (ref "R66") (pin "1") (pinfunction "1_1") (pintype "passive"))
    )
    (net (code "66") (name "/cy_dq29") (class "Default")
      (node (ref "R73") (pin "3") (pinfunction "3_3") (pintype "passive"))
    )
    (net (code "67") (name "/cy_dq30") (class "Default")
      (node (ref "R74") (pin "4") (pinfunction "4_4") (pintype "passive"))
    )
    (net (code "68") (name "/cy_dq31") (class "Default")
      (node (ref "R73") (pin "4") (pinfunction "4_4") (pintype "passive"))
    )
    (net (code "69") (name "/cy_g") (class "Default")
      (node (ref "D10") (pin "D7") (pinfunction "CLKIN_D7") (pintype "passive"))
      (node (ref "VG1") (pin "3") (pinfunction "Out_3") (pintype "passive"))
    )
    (net (code "70") (name "/cy_pclk") (class "Default")
      (node (ref "R64") (pin "3") (pinfunction "3_3") (pintype "passive"))
    )
    (net (code "71") (name "/cy_scl") (class "Default")
      (node (ref "D10") (pin "D9") (pinfunction "I2C-GPIO58_SCL_D9") (pintype "output"))
      (node (ref "D11") (pin "6") (pinfunction "SCL_6") (pintype "input"))
      (node (ref "R75") (pin "1") (pinfunction "1_1") (pintype "passive"))
    )
    (net (code "72") (name "/cy_sda") (class "Default")
      (node (ref "D10") (pin "D10") (pinfunction "I2C-GPIO59_SDA_D10") (pintype "passive"))
      (node (ref "D11") (pin "5") (pinfunction "SDA_5") (pintype "bidirectional"))
      (node (ref "R76") (pin "1") (pinfunction "1_1") (pintype "passive"))
    )
    (net (code "73") (name "/d0") (class "Default")
      (node (ref "D10") (pin "F10") (pinfunction "DQ0_F10") (pintype "passive"))
      (node (ref "R74") (pin "6") (pinfunction "6_6") (pintype "passive"))
    )
    (net (code "74") (name "/d1") (class "Default")
      (node (ref "D10") (pin "F9") (pinfunction "DQ1_F9") (pintype "passive"))
      (node (ref "R67") (pin "6") (pinfunction "6_6") (pintype "passive"))
    )
    (net (code "75") (name "/d2") (class "Default")
      (node (ref "D10") (pin "F7") (pinfunction "DQ2_F7") (pintype "passive"))
      (node (ref "R67") (pin "8") (pinfunction "8_8") (pintype "passive"))
    )
    (net (code "76") (name "/d3") (class "Default")
      (node (ref "D10") (pin "G10") (pinfunction "DQ3_G10") (pintype "passive"))
      (node (ref "R74") (pin "7") (pinfunction "7_7") (pintype "passive"))
    )
    (net (code "77") (name "/d4") (class "Default")
      (node (ref "D10") (pin "G9") (pinfunction "DQ4_G9") (pintype "passive"))
      (node (ref "R65") (pin "6") (pinfunction "6_6") (pintype "passive"))
    )
    (net (code "78") (name "/d5") (class "Default")
      (node (ref "D10") (pin "F8") (pinfunction "DQ5_F8") (pintype "passive"))
      (node (ref "R67") (pin "7") (pinfunction "7_7") (pintype "passive"))
    )
    (net (code "79") (name "/d6") (class "Default")
      (node (ref "D10") (pin "H10") (pinfunction "DQ6_H10") (pintype "passive"))
      (node (ref "R74") (pin "8") (pinfunction "8_8") (pintype "passive"))
    )
    (net (code "80") (name "/d7") (class "Default")
      (node (ref "D10") (pin "H9") (pinfunction "DQ7_H9") (pintype "passive"))
      (node (ref "R65") (pin "7") (pinfunction "7_7") (pintype "passive"))
    )
    (net (code "81") (name "/d8") (class "Default")
      (node (ref "D10") (pin "J10") (pinfunction "DQ8_J10") (pintype "passive"))
      (node (ref "R58") (pin "5") (pinfunction "5_5") (pintype "passive"))
    )
    (net (code "82") (name "/d9") (class "Default")
      (node (ref "D10") (pin "J9") (pinfunction "DQ9_J9") (pintype "passive"))
      (node (ref "R71") (pin "7") (pinfunction "7_7") (pintype "passive"))
    )
    (net (code "83") (name "/d10") (class "Default")
      (node (ref "D10") (pin "K11") (pinfunction "DQ10_K11") (pintype "passive"))
      (node (ref "R58") (pin "6") (pinfunction "6_6") (pintype "passive"))
    )
    (net (code "84") (name "/d11") (class "Default")
      (node (ref "D10") (pin "L10") (pinfunction "DQ11_L10") (pintype "passive"))
      (node (ref "R58") (pin "8") (pinfunction "8_8") (pintype "passive"))
    )
    (net (code "85") (name "/d12") (class "Default")
      (node (ref "D10") (pin "K10") (pinfunction "DQ12_K10") (pintype "passive"))
      (node (ref "R58") (pin "7") (pinfunction "7_7") (pintype "passive"))
    )
    (net (code "86") (name "/d13") (class "Default")
      (node (ref "D10") (pin "K9") (pinfunction "DQ13_K9") (pintype "passive"))
      (node (ref "R69") (pin "5") (pinfunction "5_5") (pintype "passive"))
    )
    (net (code "87") (name "/d14") (class "Default")
      (node (ref "D10") (pin "J8") (pinfunction "DQ14_J8") (pintype "passive"))
      (node (ref "R71") (pin "6") (pinfunction "6_6") (pintype "passive"))
    )
    (net (code "88") (name "/d15") (class "Default")
      (node (ref "D10") (pin "G8") (pinfunction "DQ15_G8") (pintype "passive"))
      (node (ref "R65") (pin "5") (pinfunction "5_5") (pintype "passive"))
    )
    (net (code "89") (name "/d16") (class "Default")
      (node (ref "D10") (pin "K2") (pinfunction "DQ16_K2") (pintype "passive"))
      (node (ref "R70") (pin "6") (pinfunction "6_6") (pintype "passive"))
    )
    (net (code "90") (name "/d17") (class "Default")
      (node (ref "D10") (pin "J4") (pinfunction "DQ17_J4") (pintype "passive"))
      (node (ref "R66") (pin "5") (pinfunction "5_5") (pintype "passive"))
    )
    (net (code "91") (name "/d18") (class "Default")
      (node (ref "D10") (pin "K1") (pinfunction "DQ18_K1") (pintype "passive"))
      (node (ref "R70") (pin "7") (pinfunction "7_7") (pintype "passive"))
    )
    (net (code "92") (name "/d19") (class "Default")
      (node (ref "D10") (pin "J2") (pinfunction "DQ19_J2") (pintype "passive"))
      (node (ref "R70") (pin "8") (pinfunction "8_8") (pintype "passive"))
    )
    (net (code "93") (name "/d20") (class "Default")
      (node (ref "D10") (pin "J3") (pinfunction "DQ20_J3") (pintype "passive"))
      (node (ref "R72") (pin "8") (pinfunction "8_8") (pintype "passive"))
    )
    (net (code "94") (name "/d21") (class "Default")
      (node (ref "D10") (pin "J1") (pinfunction "DQ21_J1") (pintype "passive"))
      (node (ref "R63") (pin "5") (pinfunction "5_5") (pintype "passive"))
    )
    (net (code "95") (name "/d22") (class "Default")
      (node (ref "D10") (pin "H2") (pinfunction "DQ22_H2") (pintype "passive"))
      (node (ref "R63") (pin "6") (pinfunction "6_6") (pintype "passive"))
    )
    (net (code "96") (name "/d23") (class "Default")
      (node (ref "D10") (pin "H3") (pinfunction "DQ23_H3") (pintype "passive"))
      (node (ref "R72") (pin "6") (pinfunction "6_6") (pintype "passive"))
    )
    (net (code "97") (name "/d24") (class "Default")
      (node (ref "D10") (pin "F4") (pinfunction "DQ24_F4") (pintype "passive"))
      (node (ref "R72") (pin "7") (pinfunction "7_7") (pintype "passive"))
    )
    (net (code "98") (name "/d25") (class "Default")
      (node (ref "D10") (pin "G2") (pinfunction "DQ25_G2") (pintype "passive"))
      (node (ref "R63") (pin "7") (pinfunction "7_7") (pintype "passive"))
    )
    (net (code "99") (name "/d26") (class "Default")
      (node (ref "D10") (pin "G3") (pinfunction "DQ26_G3") (pintype "passive"))
      (node (ref "R72") (pin "5") (pinfunction "5_5") (pintype "passive"))
    )
    (net (code "100") (name "/d27") (class "Default")
      (node (ref "D10") (pin "F3") (pinfunction "DQ27_F3") (pintype "passive"))
      (node (ref "R63") (pin "8") (pinfunction "8_8") (pintype "passive"))
    )
    (net (code "101") (name "/d28") (class "Default")
      (node (ref "D10") (pin "F5") (pinfunction "DQ28_F5") (pintype "passive"))
      (node (ref "R66") (pin "8") (pinfunction "8_8") (pintype "passive"))
    )
    (net (code "102") (name "/d29") (class "Default")
      (node (ref "D10") (pin "E1") (pinfunction "DQ29_E1") (pintype "passive"))
      (node (ref "R73") (pin "6") (pinfunction "6_6") (pintype "passive"))
    )
    (net (code "103") (name "/d30") (class "Default")
      (node (ref "D10") (pin "E5") (pinfunction "DQ30_E5") (pintype "passive"))
      (node (ref "R74") (pin "5") (pinfunction "5_5") (pintype "passive"))
    )
    (net (code "104") (name "/d31") (class "Default")
      (node (ref "D10") (pin "E4") (pinfunction "DQ31_E4") (pintype "passive"))
      (node (ref "R73") (pin "5") (pinfunction "5_5") (pintype "passive"))
    )
    (net (code "105") (name "/ss_rx_N") (class "Default")
      (node (ref "D10") (pin "A3") (pinfunction "SSRXM_A3") (pintype "passive"))
      (node (ref "X4") (pin "8") (pinfunction "SSRx-_8") (pintype "passive"))
    )
    (net (code "106") (name "/ss_rx_P") (class "Default")
      (node (ref "D10") (pin "A4") (pinfunction "SSRXP_A4") (pintype "passive"))
      (node (ref "X4") (pin "9") (pinfunction "SSRx+_9") (pintype "passive"))
    )
    (net (code "107") (name "/ss_tx_N") (class "Default")
      (node (ref "C181") (pin "1") (pinfunction "1_1") (pintype "passive"))
      (node (ref "X4") (pin "5") (pinfunction "SSTx-_5") (pintype "passive"))
    )
    (net (code "108") (name "/ss_tx_P") (class "Default")
      (node (ref "C180") (pin "1") (pinfunction "1_1") (pintype "passive"))
      (node (ref "X4") (pin "6") (pinfunction "SSTx+_6") (pintype "passive"))
    )
    (net (code "109") (name "/usb_N") (class "Default")
      (node (ref "D10") (pin "A10") (pinfunction "DM_A10") (pintype "passive"))
      (node (ref "X4") (pin "2") (pinfunction "D-_2") (pintype "passive"))
    )
    (net (code "110") (name "/usb_P") (class "Default")
      (node (ref "D10") (pin "A9") (pinfunction "DP_A9") (pintype "passive"))
      (node (ref "X4") (pin "3") (pinfunction "D+_3") (pintype "passive"))
    )
    (net (code "111") (name "/v1p2d") (class "Default")
      (node (ref "C184") (pin "2") (pinfunction "2_2") (pintype "passive"))
      (node (ref "C192") (pin "2") (pinfunction "2_2") (pintype "passive"))
      (node (ref "C193") (pin "2") (pinfunction "2_2") (pintype "passive"))
      (node (ref "C194") (pin "2") (pinfunction "2_2") (pintype "passive"))
      (node (ref "C195") (pin "2") (pinfunction "2_2") (pintype "passive"))
      (node (ref "C196") (pin "2") (pinfunction "2_2") (pintype "passive"))
      (node (ref "C197") (pin "2") (pinfunction "2_2") (pintype "passive"))
      (node (ref "C198") (pin "2") (pinfunction "2_2") (pintype "passive"))
      (node (ref "C199") (pin "2") (pinfunction "2_2") (pintype "passive"))
      (node (ref "C200") (pin "2") (pinfunction "2_2") (pintype "passive"))
      (node (ref "C201") (pin "2") (pinfunction "2_2") (pintype "passive"))
      (node (ref "D10") (pin "B10") (pinfunction "VDD_EFVDDQ_B10") (pintype "passive"))
      (node (ref "D10") (pin "C3") (pinfunction "VDD2_C3") (pintype "passive"))
      (node (ref "D10") (pin "E9") (pinfunction "VDD4_E9") (pintype "passive"))
      (node (ref "D10") (pin "F11") (pinfunction "VDD5_F11") (pintype "passive"))
      (node (ref "D10") (pin "H1") (pinfunction "VDD1_H1") (pintype "passive"))
      (node (ref "D10") (pin "J11") (pinfunction "VDD_SRAM_VDD2_J11") (pintype "passive"))
      (node (ref "D10") (pin "L5") (pinfunction "VDD_SRAM_VDD1_L5") (pintype "passive"))
      (node (ref "D10") (pin "L7") (pinfunction "VDD3_L7") (pintype "passive"))
      (node (ref "D12") (pin "10") (pinfunction "Vout_10") (pintype "passive"))
      (node (ref "D12") (pin "11") (pinfunction "Vout_11") (pintype "passive"))
      (node (ref "D12") (pin "12") (pinfunction "Vout_12") (pintype "passive"))
      (node (ref "D12") (pin "13") (pinfunction "Vout_13") (pintype "passive"))
      (node (ref "D12") (pin "14") (pinfunction "Vout_14") (pintype "passive"))
      (node (ref "L10") (pin "1") (pinfunction "1_1") (pintype "passive"))
      (node (ref "L11") (pin "1") (pinfunction "1_1") (pintype "passive"))
      (node (ref "L12") (pin "1") (pinfunction "1_1") (pintype "passive"))
      (node (ref "R82") (pin "2") (pinfunction "2_2") (pintype "passive"))
    )
    (net (code "112") (name "/v1p8d") (class "Default")
      (node (ref "L25") (pin "1") (pinfunction "1_1") (pintype "passive"))
    )
    (net (code "113") (name "/v1p8usb") (class "Default")
      (node (ref "D12") (pin "1") (pinfunction "Vin_1") (pintype "passive"))
      (node (ref "D12") (pin "15") (pinfunction "Vin_15") (pintype "passive"))
      (node (ref "D12") (pin "16") (pinfunction "Vin_16") (pintype "passive"))
      (node (ref "D12") (pin "2") (pinfunction "Vin_2") (pintype "passive"))
      (node (ref "D12") (pin "3") (pinfunction "Vin_3") (pintype "passive"))
      (node (ref "D12") (pin "4") (pinfunction "EN_4") (pintype "passive"))
      (node (ref "L25") (pin "2") (pinfunction "2_2") (pintype "passive"))
      (node (ref "R84") (pin "2") (pinfunction "2_2") (pintype "passive"))
    )
    (net (code "114") (name "/v2p5d") (class "Default")
      (node (ref "L26") (pin "1") (pinfunction "1_1") (pintype "passive"))
    )
    (net (code "115") (name "/v2p5usb") (class "Default")
      (node (ref "C202") (pin "2") (pinfunction "2_2") (pintype "passive"))
      (node (ref "C203") (pin "2") (pinfunction "2_2") (pintype "passive"))
      (node (ref "C204") (pin "2") (pinfunction "2_2") (pintype "passive"))
      (node (ref "C205") (pin "2") (pinfunction "2_2") (pintype "passive"))
      (node (ref "C206") (pin "2") (pinfunction "2_2") (pintype "passive"))
      (node (ref "C207") (pin "2") (pinfunction "2_2") (pintype "passive"))
      (node (ref "C208") (pin "2") (pinfunction "2_2") (pintype "passive"))
      (node (ref "D10") (pin "B1") (pinfunction "VIO4_B1") (pintype "passive"))
      (node (ref "D10") (pin "E3") (pinfunction "VIO3_E3") (pintype "passive"))
      (node (ref "D10") (pin "F1") (pinfunction "VIO2_F1") (pintype "passive"))
      (node (ref "D10") (pin "H11") (pinfunction "VIO1_2_H11") (pintype "passive"))
      (node (ref "D10") (pin "L9") (pinfunction "VIO1_1_L9") (pintype "passive"))
      (node (ref "L26") (pin "2") (pinfunction "2_2") (pintype "passive"))
      (node (ref "R77") (pin "2") (pinfunction "2_2") (pintype "passive"))
      (node (ref "R78") (pin "2") (pinfunction "2_2") (pintype "passive"))
    )
    (net (code "116") (name "/v3p3d") (class "Default")
      (node (ref "C209") (pin "2") (pinfunction "2_2") (pintype "passive"))
      (node (ref "C210") (pin "2") (pinfunction "2_2") (pintype "passive"))
      (node (ref "C211") (pin "2") (pinfunction "2_2") (pintype "passive"))
      (node (ref "C212") (pin "2") (pinfunction "2_2") (pintype "passive"))
      (node (ref "C213") (pin "2") (pinfunction "2_2") (pintype "passive"))
      (node (ref "C214") (pin "2") (pinfunction "2_2") (pintype "passive"))
      (node (ref "D10") (pin "B6") (pinfunction "CVDDQ_B6") (pintype "passive"))
      (node (ref "D10") (pin "C11") (pinfunction "VIO5_C11") (pintype "passive"))
      (node (ref "D10") (pin "E10") (pinfunction "VBAT_E10") (pintype "passive"))
      (node (ref "D11") (pin "8") (pinfunction "VCC_8") (pintype "power_in"))
      (node (ref "R108") (pin "1") (pinfunction "1_1") (pintype "passive"))
      (node (ref "R62") (pin "1") (pinfunction "1_1") (pintype "passive"))
      (node (ref "R75") (pin "2") (pinfunction "2_2") (pintype "passive"))
      (node (ref "R76") (pin "2") (pinfunction "2_2") (pintype "passive"))
      (node (ref "R81") (pin "2") (pinfunction "2_2") (pintype "passive"))
      (node (ref "VG1") (pin "4") (pinfunction "Vcc_4") (pintype "passive"))
    )
    (net (code "117") (name "Net-(D10A-INT_N_CTL15)") (class "Default")
      (node (ref "D10") (pin "L8") (pinfunction "INT_N_CTL15_L8") (pintype "passive"))
      (node (ref "R80") (pin "1") (pinfunction "1_1") (pintype "passive"))
    )
    (net (code "118") (name "Net-(D10A-PMODE0)") (class "Default")
      (node (ref "D10") (pin "G4") (pinfunction "PMODE0_G4") (pintype "passive"))
      (node (ref "R77") (pin "1") (pinfunction "1_1") (pintype "passive"))
    )
    (net (code "119") (name "Net-(D10A-PMODE1)") (class "Default")
      (node (ref "D10") (pin "H4") (pinfunction "PMODE1_H4") (pintype "passive"))
      (node (ref "R78") (pin "1") (pinfunction "1_1") (pintype "passive"))
    )
    (net (code "120") (name "Net-(D10A-PMODE2)") (class "Default")
      (node (ref "D10") (pin "L4") (pinfunction "PMODE2_L4") (pintype "passive"))
      (node (ref "R79") (pin "1") (pinfunction "1_1") (pintype "passive"))
    )
    (net (code "121") (name "Net-(D10A-RESET_N)") (class "Default")
      (node (ref "C187") (pin "2") (pinfunction "2_2") (pintype "passive"))
      (node (ref "D10") (pin "C5") (pinfunction "RESET_N_C5") (pintype "passive"))
      (node (ref "R81") (pin "1") (pinfunction "1_1") (pintype "passive"))
    )
    (net (code "122") (name "Net-(D10D-OTG_ID)") (class "Default")
      (node (ref "D10") (pin "C9") (pinfunction "OTG_ID_C9") (pintype "passive"))
      (node (ref "R60") (pin "1") (pinfunction "1_1") (pintype "passive"))
    )
    (net (code "123") (name "Net-(D10D-R_USB2)") (class "Default")
      (node (ref "D10") (pin "C8") (pinfunction "R_USB2_C8") (pintype "passive"))
      (node (ref "R109") (pin "1") (pinfunction "1_1") (pintype "passive"))
    )
    (net (code "124") (name "Net-(D10D-R_USB3)") (class "Default")
      (node (ref "D10") (pin "B3") (pinfunction "R_USB3_B3") (pintype "passive"))
      (node (ref "R68") (pin "1") (pinfunction "1_1") (pintype "passive"))
    )
    (net (code "125") (name "Net-(D10D-SSTXM)") (class "Default")
      (node (ref "C181") (pin "2") (pinfunction "2_2") (pintype "passive"))
      (node (ref "D10") (pin "A6") (pinfunction "SSTXM_A6") (pintype "passive"))
    )
    (net (code "126") (name "Net-(D10D-SSTXP)") (class "Default")
      (node (ref "C180") (pin "2") (pinfunction "2_2") (pintype "passive"))
      (node (ref "D10") (pin "A5") (pinfunction "SSTXP_A5") (pintype "passive"))
    )
    (net (code "127") (name "Net-(D10D-VBUS)") (class "Default")
      (node (ref "C179") (pin "1") (pinfunction "1_1") (pintype "passive"))
      (node (ref "D10") (pin "E11") (pinfunction "VBUS_E11") (pintype "passive"))
      (node (ref "R57") (pin "1") (pinfunction "1_1") (pintype "passive"))
    )
    (net (code "128") (name "Net-(D10E-FSLC0)") (class "Default")
      (node (ref "D10") (pin "B2") (pinfunction "FSLC0_B2") (pintype "passive"))
      (node (ref "R59") (pin "2") (pinfunction "2_2") (pintype "passive"))
    )
    (net (code "129") (name "Net-(D10E-FSLC1)") (class "Default")
      (node (ref "D10") (pin "B4") (pinfunction "FSLC1_B4") (pintype "passive"))
      (node (ref "R61") (pin "2") (pinfunction "2_2") (pintype "passive"))
    )
    (net (code "130") (name "Net-(D10E-FSLC2)") (class "Default")
      (node (ref "D10") (pin "E6") (pinfunction "FSLC2_E6") (pintype "passive"))
      (node (ref "R62") (pin "2") (pinfunction "2_2") (pintype "passive"))
    )
    (net (code "131") (name "Net-(D10E-XTALIN)") (class "Default")
      (node (ref "C183") (pin "2") (pinfunction "2_2") (pintype "passive"))
      (node (ref "D10") (pin "C6") (pinfunction "XTALIN_C6") (pintype "passive"))
      (node (ref "ZQ1") (pin "2") (pinfunction "2_2") (pintype "passive"))
    )
    (net (code "132") (name "Net-(D10E-XTALOUT)") (class "Default")
      (node (ref "C182") (pin "2") (pinfunction "2_2") (pintype "passive"))
      (node (ref "D10") (pin "C7") (pinfunction "XTALOUT_C7") (pintype "passive"))
      (node (ref "ZQ1") (pin "1") (pinfunction "1_1") (pintype "passive"))
    )
    (net (code "133") (name "Net-(D12-Adj)") (class "Default")
      (node (ref "D12") (pin "9") (pinfunction "Adj_9") (pintype "passive"))
      (node (ref "R82") (pin "1") (pinfunction "1_1") (pintype "passive"))
      (node (ref "R83") (pin "2") (pinfunction "2_2") (pintype "passive"))
    )
    (net (code "134") (name "Net-(D12-PG)") (class "Default")
      (node (ref "D12") (pin "5") (pinfunction "PG_5") (pintype "passive"))
      (node (ref "R84") (pin "1") (pinfunction "1_1") (pintype "passive"))
    )
    (net (code "135") (name "Net-(VG1-EN)") (class "Default")
      (node (ref "R108") (pin "2") (pinfunction "2_2") (pintype "passive"))
      (node (ref "VG1") (pin "1") (pinfunction "EN_1") (pintype "passive"))
    )
    (net (code "136") (name "Net-(X4-VBUS)") (class "Default")
      (node (ref "R57") (pin "2") (pinfunction "2_2") (pintype "passive"))
      (node (ref "X4") (pin "1") (pinfunction "VBUS_1") (pintype "passive"))
    )
    (net (code "137") (name "unconnected-(D10B-GPIO45-PadF2)") (class "Default")
      (node (ref "D10") (pin "F2") (pinfunction "GPIO45_F2") (pintype "passive"))
    )
    (net (code "138") (name "unconnected-(D10C-I2S-CLK-PadD1)") (class "Default")
      (node (ref "D10") (pin "D1") (pinfunction "I2S-CLK_D1") (pintype "passive"))
    )
    (net (code "139") (name "unconnected-(D10C-I2S-MCLK-PadC4)") (class "Default")
      (node (ref "D10") (pin "C4") (pinfunction "I2S-MCLK_C4") (pintype "passive"))
    )
    (net (code "140") (name "unconnected-(D10C-UART-TX_SPI-MISO-PadC2)") (class "Default")
      (node (ref "D10") (pin "C2") (pinfunction "UART-TX_SPI-MISO_C2") (pintype "passive"))
    )
    (net (code "141") (name "unconnected-(D10D-NC-PadA11)") (class "Default")
      (node (ref "D10") (pin "A11") (pinfunction "NC_A11") (pintype "passive"))
    )
    (net (code "142") (name "unconnected-(D10E-CLKIN_32-PadD6)") (class "Default")
      (node (ref "D10") (pin "D6") (pinfunction "CLKIN_32_D6") (pintype "passive"))
    )
    (net (code "143") (name "unconnected-(D10F-I2C-GPIO60_CHARGER-DETECT-PadD11)") (class "Default")
      (node (ref "D10") (pin "D11") (pinfunction "I2C-GPIO60_CHARGER-DETECT_D11") (pintype "passive"))
    )
    (net (code "144") (name "unconnected-(D10F-TCK-PadF6)") (class "Default")
      (node (ref "D10") (pin "F6") (pinfunction "TCK_F6") (pintype "passive"))
    )
    (net (code "145") (name "unconnected-(D10F-TDI-PadE7)") (class "Default")
      (node (ref "D10") (pin "E7") (pinfunction "TDI_E7") (pintype "passive"))
    )
    (net (code "146") (name "unconnected-(D10F-TDO-PadC10)") (class "Default")
      (node (ref "D10") (pin "C10") (pinfunction "TDO_C10") (pintype "passive"))
    )
    (net (code "147") (name "unconnected-(D10F-TMS-PadE8)") (class "Default")
      (node (ref "D10") (pin "E8") (pinfunction "TMS_E8") (pintype "passive"))
    )
    (net (code "148") (name "unconnected-(D10F-TRST_N-PadB11)") (class "Default")
      (node (ref "D10") (pin "B11") (pinfunction "TRST_N_B11") (pintype "passive"))
    )
    (net (code "149") (name "unconnected-(D12-NC-Pad8)") (class "Default")
      (node (ref "D12") (pin "8") (pinfunction "NC_8") (pintype "passive"))
    )
    (net (code "150") (name "unconnected-(D12-SS-Pad7)") (class "Default")
      (node (ref "D12") (pin "7") (pinfunction "SS_7") (pintype "passive"))
    )
    (net (code "151") (name "unconnected-(R73-Pad1)") (class "Default")
      (node (ref "R73") (pin "1") (pinfunction "1_1") (pintype "passive"))
    )
    (net (code "152") (name "unconnected-(R73-Pad2)") (class "Default")
      (node (ref "R73") (pin "2") (pinfunction "2_2") (pintype "passive"))
    )
    (net (code "153") (name "unconnected-(R73-Pad7)") (class "Default")
      (node (ref "R73") (pin "7") (pinfunction "7_7") (pintype "passive"))
    )
    (net (code "154") (name "unconnected-(R73-Pad8)") (class "Default")
      (node (ref "R73") (pin "8") (pinfunction "8_8") (pintype "passive"))
    )
  )
)
